# design.net
KiCad netlist of a schematic drawn in Altium Designer
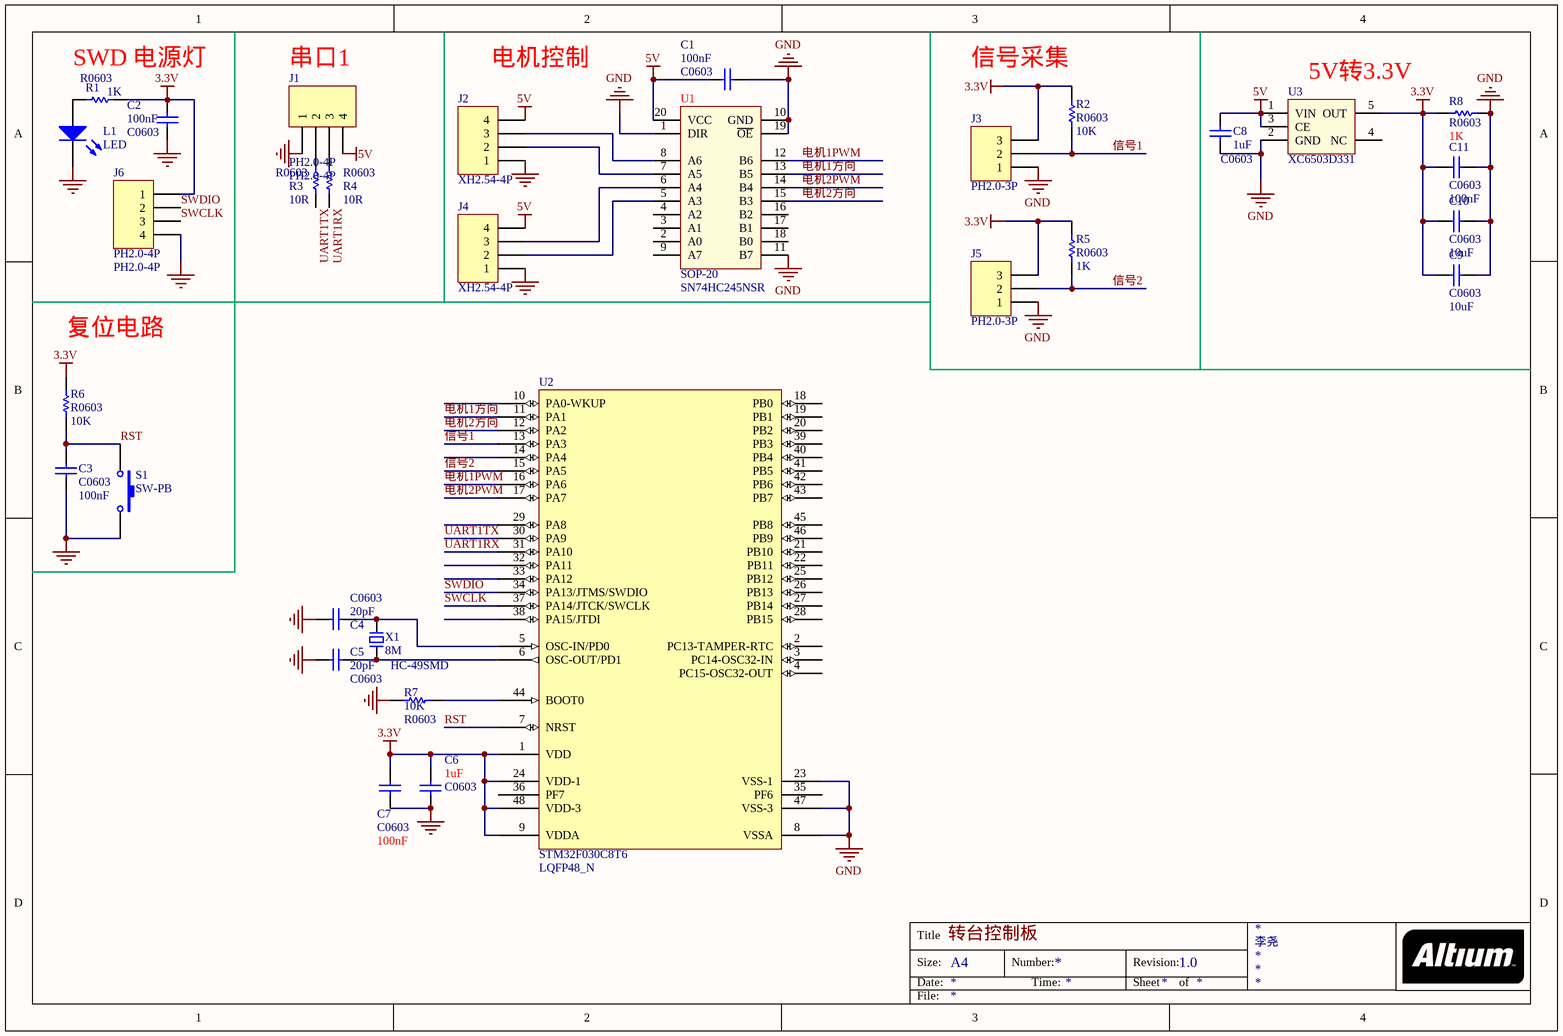
[diagram p0: 转台控制板原理图.SchDoc]

(export (version "E")
  (design (tool "Eeschema 10.0.6"))
  (components
    (comp (ref "C1")
      (value "C0603")
      (footprint "C0603_M1608")
      (description "Capacitor")
      (fields (field (name "ALTIUM_VALUE") "100nF") (field (name "PUBLISHER") "Altium Limited"))
      (libsource (lib "Miscellaneous Devices") (part "Cap"))
    )
    (comp (ref "C2")
      (value "C0603")
      (footprint "C0603_M1608")
      (description "Capacitor")
      (fields (field (name "ALTIUM_VALUE") "100nF") (field (name "PUBLISHER") "Altium Limited"))
      (libsource (lib "Miscellaneous Devices") (part "Cap"))
    )
    (comp (ref "C3")
      (value "C0603")
      (footprint "C0603_M1608")
      (description "Capacitor")
      (fields (field (name "ALTIUM_VALUE") "100nF") (field (name "PUBLISHER") "Altium Limited"))
      (libsource (lib "Miscellaneous Devices") (part "Cap"))
    )
    (comp (ref "C4")
      (value "C0603")
      (footprint "C0603_M1608")
      (description "Capacitor")
      (fields (field (name "ALTIUM_VALUE") "20pF") (field (name "PUBLISHER") "Altium Limited"))
      (libsource (lib "Miscellaneous Devices") (part "Cap"))
    )
    (comp (ref "C5")
      (value "C0603")
      (footprint "C0603_M1608")
      (description "Capacitor")
      (fields (field (name "ALTIUM_VALUE") "20pF") (field (name "PUBLISHER") "Altium Limited"))
      (libsource (lib "Miscellaneous Devices") (part "Cap"))
    )
    (comp (ref "C6")
      (value "C0603")
      (footprint "C0603_M1608")
      (description "Capacitor")
      (fields (field (name "ALTIUM_VALUE") "1uF") (field (name "PUBLISHER") "Altium Limited"))
      (libsource (lib "Miscellaneous Devices") (part "Cap"))
    )
    (comp (ref "C7")
      (value "C0603")
      (footprint "C0603_M1608")
      (description "Capacitor")
      (fields (field (name "ALTIUM_VALUE") "100nF") (field (name "PUBLISHER") "Altium Limited"))
      (libsource (lib "Miscellaneous Devices") (part "Cap"))
    )
    (comp (ref "C8")
      (value "C0603")
      (footprint "C0603_M1608")
      (description "Capacitor")
      (fields (field (name "ALTIUM_VALUE") "1uF") (field (name "PUBLISHER") "Altium Limited"))
      (libsource (lib "Miscellaneous Devices") (part "Cap"))
    )
    (comp (ref "C9")
      (value "C0603")
      (footprint "C0603_M1608")
      (description "Capacitor")
      (fields (field (name "ALTIUM_VALUE") "10uF") (field (name "PUBLISHER") "Altium Limited"))
      (libsource (lib "Miscellaneous Devices") (part "Cap"))
    )
    (comp (ref "C10")
      (value "C0603")
      (footprint "C0603_M1608")
      (description "Capacitor")
      (fields (field (name "ALTIUM_VALUE") "10uF") (field (name "PUBLISHER") "Altium Limited"))
      (libsource (lib "Miscellaneous Devices") (part "Cap"))
    )
    (comp (ref "C11")
      (value "C0603")
      (footprint "C0603_M1608")
      (description "Capacitor")
      (fields (field (name "ALTIUM_VALUE") "100nF") (field (name "PUBLISHER") "Altium Limited"))
      (libsource (lib "Miscellaneous Devices") (part "Cap"))
    )
    (comp (ref "J1")
      (value "PH2.0-4P")
      (footprint "PH2.0-4P")
      (description "Header, 4-Pin")
      (fields (field (name "ALTIUM_VALUE") "PH2.0-4P") (field (name "PUBLISHER") "Altium Limited"))
      (libsource (lib "") (part "Header 4_1"))
    )
    (comp (ref "J2")
      (value "XH2.54-4P")
      (footprint "XH2.54-4")
      (description "Header, 4-Pin")
      (fields (field (name "PUBLISHER") "Altium Limited"))
      (libsource (lib "") (part "Header 4_2"))
    )
    (comp (ref "J3")
      (value "PH2.0-3P")
      (footprint "PH2.0-3P")
      (description "Header, 3-Pin")
      (fields (field (name "PUBLISHER") "Altium Limited"))
      (libsource (lib "Sparks") (part "Header 3"))
    )
    (comp (ref "J4")
      (value "XH2.54-4P")
      (footprint "XH2.54-4")
      (description "Header, 4-Pin")
      (fields (field (name "PUBLISHER") "Altium Limited"))
      (libsource (lib "") (part "Header 4_2"))
    )
    (comp (ref "J5")
      (value "PH2.0-3P")
      (footprint "PH2.0-3P")
      (description "Header, 3-Pin")
      (fields (field (name "PUBLISHER") "Altium Limited"))
      (libsource (lib "Sparks") (part "Header 3"))
    )
    (comp (ref "J6")
      (value "PH2.0-4P")
      (footprint "PH2.0-4P")
      (description "Header, 4-Pin")
      (fields (field (name "ALTIUM_VALUE") "PH2.0-4P") (field (name "PUBLISHER") "Altium Limited"))
      (libsource (lib "Miscellaneous Connectors") (part "Header 4"))
    )
    (comp (ref "L1") (value "LED") (footprint "C2012") (libsource (lib "Sparks") (part "LED")))
    (comp (ref "R1")
      (value "R0603")
      (footprint "0603")
      (description "Resistor")
      (fields (field (name "ALTIUM_VALUE") "1K") (field (name "PUBLISHER") "Altium Limited"))
      (libsource (lib "Miscellaneous Devices") (part "Res1"))
    )
    (comp (ref "R2")
      (value "R0603")
      (footprint "0603")
      (description "Resistor")
      (fields (field (name "ALTIUM_VALUE") "10K") (field (name "PUBLISHER") "Altium Limited"))
      (libsource (lib "Miscellaneous Devices") (part "Res1"))
    )
    (comp (ref "R3")
      (value "R0603")
      (footprint "0603")
      (description "Resistor")
      (fields (field (name "ALTIUM_VALUE") "10R") (field (name "PUBLISHER") "Altium Limited"))
      (libsource (lib "Miscellaneous Devices") (part "Res1"))
    )
    (comp (ref "R4")
      (value "R0603")
      (footprint "0603")
      (description "Resistor")
      (fields (field (name "ALTIUM_VALUE") "10R") (field (name "PUBLISHER") "Altium Limited"))
      (libsource (lib "Miscellaneous Devices") (part "Res1"))
    )
    (comp (ref "R5")
      (value "R0603")
      (footprint "0603")
      (description "Resistor")
      (fields (field (name "ALTIUM_VALUE") "1K") (field (name "PUBLISHER") "Altium Limited"))
      (libsource (lib "Miscellaneous Devices") (part "Res1"))
    )
    (comp (ref "R6")
      (value "R0603")
      (footprint "0603")
      (description "Resistor")
      (fields (field (name "ALTIUM_VALUE") "10K") (field (name "PUBLISHER") "Altium Limited"))
      (libsource (lib "Miscellaneous Devices") (part "Res1"))
    )
    (comp (ref "R7")
      (value "R0603")
      (footprint "0603")
      (description "Resistor")
      (fields (field (name "ALTIUM_VALUE") "10K") (field (name "PUBLISHER") "Altium Limited"))
      (libsource (lib "Miscellaneous Devices") (part "Res1"))
    )
    (comp (ref "R8")
      (value "R0603")
      (footprint "0603")
      (description "Resistor")
      (fields (field (name "ALTIUM_VALUE") "1K") (field (name "PUBLISHER") "Altium Limited"))
      (libsource (lib "Miscellaneous Devices") (part "Res1"))
    )
    (comp (ref "S1")
      (value "SW-PB")
      (footprint "SPST-2")
      (description "Switch")
      (fields (field (name "PUBLISHER") "Altium Limited"))
      (libsource (lib "Miscellaneous Devices") (part "SW-PB"))
    )
    (comp (ref "U1")
      (value "SOP-20")
      (footprint "SOP-20")
      (fields (field (name "ALTIUM_VALUE") "SN74HC245NSR"))
      (libsource (lib "SCH") (part "74HC245"))
    )
    (comp (ref "U2")
      (value "LQFP48_N")
      (footprint "LQFP48_N")
      (description "STM32 ARM-based 32-bit MCU with 64 Kbytes Flash, 48-pin LQFP, Industrial Temperature")
      (fields (field (name "ALTIUM_VALUE") "STM32F030C8T6") (field (name "PUBLISHER") "*"))
      (libsource (lib "ST Microcontroller 32-Bit STM32 SCH") (part "STM32F103C8T6"))
    )
    (comp (ref "U3")
      (value "XC6503D331")
      (footprint "SOT23-5")
      (libsource (lib "CYSchlib") (part "XC6503Dxxx"))
    )
    (comp (ref "X1")
      (value "8M")
      (footprint "HC-49SMD")
      (fields (field (name "ALTIUM_VALUE") "HC-49SMD"))
      (libsource (lib "CYSchlib") (part "XTAL"))
    )
  )
  (nets
    (net (code "1") (name "/RST") (class "Default")
      (node (ref "C3") (pin "1") (pinfunction "1_1") (pintype "passive"))
      (node (ref "R6") (pin "2") (pinfunction "2_2") (pintype "passive"))
      (node (ref "S1") (pin "1") (pinfunction "1_1") (pintype "passive"))
      (node (ref "U2") (pin "7") (pinfunction "NRST_7") (pintype "bidirectional"))
    )
    (net (code "2") (name "/SWCLK") (class "Default")
      (node (ref "J6") (pin "3") (pinfunction "3_3") (pintype "passive"))
      (node (ref "U2") (pin "37") (pinfunction "PA14/JTCK/SWCLK_37") (pintype "bidirectional"))
    )
    (net (code "3") (name "/SWDIO") (class "Default")
      (node (ref "J6") (pin "2") (pinfunction "2_2") (pintype "passive"))
      (node (ref "U2") (pin "34") (pinfunction "PA13/JTMS/SWDIO_34") (pintype "bidirectional"))
    )
    (net (code "4") (name "/UART1RX") (class "Default")
      (node (ref "R4") (pin "2") (pinfunction "2_2") (pintype "passive"))
      (node (ref "U2") (pin "31") (pinfunction "PA10_31") (pintype "bidirectional"))
    )
    (net (code "5") (name "/UART1TX") (class "Default")
      (node (ref "R3") (pin "2") (pinfunction "2_2") (pintype "passive"))
      (node (ref "U2") (pin "30") (pinfunction "PA9_30") (pintype "bidirectional"))
    )
    (net (code "6") (name "/信号1") (class "Default")
      (node (ref "J3") (pin "2") (pinfunction "2_2") (pintype "passive"))
      (node (ref "R2") (pin "2") (pinfunction "2_2") (pintype "passive"))
      (node (ref "U2") (pin "13") (pinfunction "PA3_13") (pintype "bidirectional"))
    )
    (net (code "7") (name "/信号2") (class "Default")
      (node (ref "J5") (pin "2") (pinfunction "2_2") (pintype "passive"))
      (node (ref "R5") (pin "2") (pinfunction "2_2") (pintype "passive"))
      (node (ref "U2") (pin "15") (pinfunction "PA5_15") (pintype "bidirectional"))
    )
    (net (code "8") (name "/电机1PWM") (class "Default")
      (node (ref "U1") (pin "12") (pinfunction "B6_12") (pintype "passive"))
      (node (ref "U2") (pin "16") (pinfunction "PA6_16") (pintype "bidirectional"))
    )
    (net (code "9") (name "/电机1方向") (class "Default")
      (node (ref "U1") (pin "13") (pinfunction "B5_13") (pintype "passive"))
      (node (ref "U2") (pin "11") (pinfunction "PA1_11") (pintype "bidirectional"))
    )
    (net (code "10") (name "/电机2PWM") (class "Default")
      (node (ref "U1") (pin "14") (pinfunction "B4_14") (pintype "passive"))
      (node (ref "U2") (pin "17") (pinfunction "PA7_17") (pintype "bidirectional"))
    )
    (net (code "11") (name "/电机2方向") (class "Default")
      (node (ref "U1") (pin "15") (pinfunction "B3_15") (pintype "passive"))
      (node (ref "U2") (pin "12") (pinfunction "PA2_12") (pintype "bidirectional"))
    )
    (net (code "12") (name "3.3V") (class "Default")
      (node (ref "C10") (pin "2") (pinfunction "2_2") (pintype "passive"))
      (node (ref "C11") (pin "2") (pinfunction "2_2") (pintype "passive"))
      (node (ref "C2") (pin "1") (pinfunction "1_1") (pintype "passive"))
      (node (ref "C6") (pin "1") (pinfunction "1_1") (pintype "passive"))
      (node (ref "C7") (pin "1") (pinfunction "1_1") (pintype "passive"))
      (node (ref "C9") (pin "1") (pinfunction "1_1") (pintype "passive"))
      (node (ref "J3") (pin "3") (pinfunction "3_3") (pintype "passive"))
      (node (ref "J5") (pin "3") (pinfunction "3_3") (pintype "passive"))
      (node (ref "J6") (pin "1") (pinfunction "1_1") (pintype "passive"))
      (node (ref "R1") (pin "2") (pinfunction "2_2") (pintype "passive"))
      (node (ref "R2") (pin "1") (pinfunction "1_1") (pintype "passive"))
      (node (ref "R5") (pin "1") (pinfunction "1_1") (pintype "passive"))
      (node (ref "R6") (pin "1") (pinfunction "1_1") (pintype "passive"))
      (node (ref "R8") (pin "2") (pinfunction "2_2") (pintype "passive"))
      (node (ref "U2") (pin "1") (pinfunction "VDD_1") (pintype "power_in"))
      (node (ref "U2") (pin "24") (pinfunction "VDD-1_24") (pintype "power_in"))
      (node (ref "U2") (pin "48") (pinfunction "VDD-3_48") (pintype "power_in"))
      (node (ref "U2") (pin "9") (pinfunction "VDDA_9") (pintype "power_in"))
      (node (ref "U3") (pin "5") (pinfunction "OUT_5") (pintype "passive"))
    )
    (net (code "13") (name "5V") (class "Default")
      (node (ref "C1") (pin "1") (pinfunction "1_1") (pintype "passive"))
      (node (ref "C8") (pin "2") (pinfunction "2_2") (pintype "passive"))
      (node (ref "J1") (pin "4") (pinfunction "4_4") (pintype "passive"))
      (node (ref "J2") (pin "4") (pinfunction "4_4") (pintype "passive"))
      (node (ref "J4") (pin "4") (pinfunction "4_4") (pintype "passive"))
      (node (ref "U1") (pin "20") (pinfunction "VCC_20") (pintype "passive"))
      (node (ref "U3") (pin "1") (pinfunction "VIN_1") (pintype "passive"))
      (node (ref "U3") (pin "3") (pinfunction "CE_3") (pintype "passive"))
    )
    (net (code "14") (name "GND") (class "Default")
      (node (ref "C1") (pin "2") (pinfunction "2_2") (pintype "passive"))
      (node (ref "C10") (pin "1") (pinfunction "1_1") (pintype "passive"))
      (node (ref "C11") (pin "1") (pinfunction "1_1") (pintype "passive"))
      (node (ref "C2") (pin "2") (pinfunction "2_2") (pintype "passive"))
      (node (ref "C3") (pin "2") (pinfunction "2_2") (pintype "passive"))
      (node (ref "C4") (pin "1") (pinfunction "1_1") (pintype "passive"))
      (node (ref "C5") (pin "1") (pinfunction "1_1") (pintype "passive"))
      (node (ref "C6") (pin "2") (pinfunction "2_2") (pintype "passive"))
      (node (ref "C7") (pin "2") (pinfunction "2_2") (pintype "passive"))
      (node (ref "C8") (pin "1") (pinfunction "1_1") (pintype "passive"))
      (node (ref "C9") (pin "2") (pinfunction "2_2") (pintype "passive"))
      (node (ref "J1") (pin "1") (pinfunction "1_1") (pintype "passive"))
      (node (ref "J2") (pin "1") (pinfunction "1_1") (pintype "passive"))
      (node (ref "J3") (pin "1") (pinfunction "1_1") (pintype "passive"))
      (node (ref "J4") (pin "1") (pinfunction "1_1") (pintype "passive"))
      (node (ref "J5") (pin "1") (pinfunction "1_1") (pintype "passive"))
      (node (ref "J6") (pin "4") (pinfunction "4_4") (pintype "passive"))
      (node (ref "L1") (pin "2") (pinfunction "K_2") (pintype "passive"))
      (node (ref "R7") (pin "1") (pinfunction "1_1") (pintype "passive"))
      (node (ref "R8") (pin "1") (pinfunction "1_1") (pintype "passive"))
      (node (ref "S1") (pin "2") (pinfunction "2_2") (pintype "passive"))
      (node (ref "U1") (pin "1") (pinfunction "DIR_1") (pintype "passive"))
      (node (ref "U1") (pin "10") (pinfunction "GND_10") (pintype "passive"))
      (node (ref "U1") (pin "11") (pinfunction "B7_11") (pintype "passive"))
      (node (ref "U1") (pin "19") (pinfunction "~{OE}_19") (pintype "passive"))
      (node (ref "U2") (pin "23") (pinfunction "VSS-1_23") (pintype "power_in"))
      (node (ref "U2") (pin "47") (pinfunction "VSS-3_47") (pintype "power_in"))
      (node (ref "U2") (pin "8") (pinfunction "VSSA_8") (pintype "power_in"))
      (node (ref "U3") (pin "2") (pinfunction "GND_2") (pintype "passive"))
    )
    (net (code "15") (name "Net-(J1-Pad2)") (class "Default")
      (node (ref "J1") (pin "2") (pinfunction "2_2") (pintype "passive"))
      (node (ref "R3") (pin "1") (pinfunction "1_1") (pintype "passive"))
    )
    (net (code "16") (name "Net-(J1-Pad3)") (class "Default")
      (node (ref "J1") (pin "3") (pinfunction "3_3") (pintype "passive"))
      (node (ref "R4") (pin "1") (pinfunction "1_1") (pintype "passive"))
    )
    (net (code "17") (name "Net-(L1-A)") (class "Default")
      (node (ref "L1") (pin "1") (pinfunction "A_1") (pintype "passive"))
      (node (ref "R1") (pin "1") (pinfunction "1_1") (pintype "passive"))
    )
    (net (code "18") (name "Net-(U1-A3)") (class "Default")
      (node (ref "J4") (pin "2") (pinfunction "2_2") (pintype "passive"))
      (node (ref "U1") (pin "5") (pinfunction "A3_5") (pintype "passive"))
    )
    (net (code "19") (name "Net-(U1-A4)") (class "Default")
      (node (ref "J4") (pin "3") (pinfunction "3_3") (pintype "passive"))
      (node (ref "U1") (pin "6") (pinfunction "A4_6") (pintype "passive"))
    )
    (net (code "20") (name "Net-(U1-A5)") (class "Default")
      (node (ref "J2") (pin "2") (pinfunction "2_2") (pintype "passive"))
      (node (ref "U1") (pin "7") (pinfunction "A5_7") (pintype "passive"))
    )
    (net (code "21") (name "Net-(U1-A6)") (class "Default")
      (node (ref "J2") (pin "3") (pinfunction "3_3") (pintype "passive"))
      (node (ref "U1") (pin "8") (pinfunction "A6_8") (pintype "passive"))
    )
    (net (code "22") (name "Net-(U2-BOOT0)") (class "Default")
      (node (ref "R7") (pin "2") (pinfunction "2_2") (pintype "passive"))
      (node (ref "U2") (pin "44") (pinfunction "BOOT0_44") (pintype "input"))
    )
    (net (code "23") (name "Net-(U2-OSC-IN{slash}PD0)") (class "Default")
      (node (ref "C4") (pin "2") (pinfunction "2_2") (pintype "passive"))
      (node (ref "U2") (pin "5") (pinfunction "OSC-IN/PD0_5") (pintype "input"))
      (node (ref "X1") (pin "2") (pinfunction "2_2") (pintype "passive"))
    )
    (net (code "24") (name "Net-(U2-OSC-OUT{slash}PD1)") (class "Default")
      (node (ref "C5") (pin "2") (pinfunction "2_2") (pintype "passive"))
      (node (ref "U2") (pin "6") (pinfunction "OSC-OUT/PD1_6") (pintype "output"))
      (node (ref "X1") (pin "1") (pinfunction "1_1") (pintype "passive"))
    )
    (net (code "25") (name "unconnected-(U1-A0-Pad2)") (class "Default")
      (node (ref "U1") (pin "2") (pinfunction "A0_2") (pintype "passive"))
    )
    (net (code "26") (name "unconnected-(U1-A1-Pad3)") (class "Default")
      (node (ref "U1") (pin "3") (pinfunction "A1_3") (pintype "passive"))
    )
    (net (code "27") (name "unconnected-(U1-A2-Pad4)") (class "Default")
      (node (ref "U1") (pin "4") (pinfunction "A2_4") (pintype "passive"))
    )
    (net (code "28") (name "unconnected-(U1-A7-Pad9)") (class "Default")
      (node (ref "U1") (pin "9") (pinfunction "A7_9") (pintype "passive"))
    )
    (net (code "29") (name "unconnected-(U1-B0-Pad18)") (class "Default")
      (node (ref "U1") (pin "18") (pinfunction "B0_18") (pintype "passive"))
    )
    (net (code "30") (name "unconnected-(U1-B1-Pad17)") (class "Default")
      (node (ref "U1") (pin "17") (pinfunction "B1_17") (pintype "passive"))
    )
    (net (code "31") (name "unconnected-(U1-B2-Pad16)") (class "Default")
      (node (ref "U1") (pin "16") (pinfunction "B2_16") (pintype "passive"))
    )
    (net (code "32") (name "unconnected-(U2-PA0-WKUP-Pad10)") (class "Default")
      (node (ref "U2") (pin "10") (pinfunction "PA0-WKUP_10") (pintype "bidirectional"))
    )
    (net (code "33") (name "unconnected-(U2-PA4-Pad14)") (class "Default")
      (node (ref "U2") (pin "14") (pinfunction "PA4_14") (pintype "bidirectional"))
    )
    (net (code "34") (name "unconnected-(U2-PA8-Pad29)") (class "Default")
      (node (ref "U2") (pin "29") (pinfunction "PA8_29") (pintype "bidirectional"))
    )
    (net (code "35") (name "unconnected-(U2-PA11-Pad32)") (class "Default")
      (node (ref "U2") (pin "32") (pinfunction "PA11_32") (pintype "bidirectional"))
    )
    (net (code "36") (name "unconnected-(U2-PA12-Pad33)") (class "Default")
      (node (ref "U2") (pin "33") (pinfunction "PA12_33") (pintype "bidirectional"))
    )
    (net (code "37") (name "unconnected-(U2-PA15{slash}JTDI-Pad38)") (class "Default")
      (node (ref "U2") (pin "38") (pinfunction "PA15/JTDI_38") (pintype "bidirectional"))
    )
    (net (code "38") (name "unconnected-(U2-PB0-Pad18)") (class "Default")
      (node (ref "U2") (pin "18") (pinfunction "PB0_18") (pintype "bidirectional"))
    )
    (net (code "39") (name "unconnected-(U2-PB1-Pad19)") (class "Default")
      (node (ref "U2") (pin "19") (pinfunction "PB1_19") (pintype "bidirectional"))
    )
    (net (code "40") (name "unconnected-(U2-PB2-Pad20)") (class "Default")
      (node (ref "U2") (pin "20") (pinfunction "PB2_20") (pintype "bidirectional"))
    )
    (net (code "41") (name "unconnected-(U2-PB3-Pad39)") (class "Default")
      (node (ref "U2") (pin "39") (pinfunction "PB3_39") (pintype "bidirectional"))
    )
    (net (code "42") (name "unconnected-(U2-PB4-Pad40)") (class "Default")
      (node (ref "U2") (pin "40") (pinfunction "PB4_40") (pintype "bidirectional"))
    )
    (net (code "43") (name "unconnected-(U2-PB5-Pad41)") (class "Default")
      (node (ref "U2") (pin "41") (pinfunction "PB5_41") (pintype "bidirectional"))
    )
    (net (code "44") (name "unconnected-(U2-PB6-Pad42)") (class "Default")
      (node (ref "U2") (pin "42") (pinfunction "PB6_42") (pintype "bidirectional"))
    )
    (net (code "45") (name "unconnected-(U2-PB7-Pad43)") (class "Default")
      (node (ref "U2") (pin "43") (pinfunction "PB7_43") (pintype "bidirectional"))
    )
    (net (code "46") (name "unconnected-(U2-PB8-Pad45)") (class "Default")
      (node (ref "U2") (pin "45") (pinfunction "PB8_45") (pintype "bidirectional"))
    )
    (net (code "47") (name "unconnected-(U2-PB9-Pad46)") (class "Default")
      (node (ref "U2") (pin "46") (pinfunction "PB9_46") (pintype "bidirectional"))
    )
    (net (code "48") (name "unconnected-(U2-PB10-Pad21)") (class "Default")
      (node (ref "U2") (pin "21") (pinfunction "PB10_21") (pintype "bidirectional"))
    )
    (net (code "49") (name "unconnected-(U2-PB11-Pad22)") (class "Default")
      (node (ref "U2") (pin "22") (pinfunction "PB11_22") (pintype "bidirectional"))
    )
    (net (code "50") (name "unconnected-(U2-PB12-Pad25)") (class "Default")
      (node (ref "U2") (pin "25") (pinfunction "PB12_25") (pintype "bidirectional"))
    )
    (net (code "51") (name "unconnected-(U2-PB13-Pad26)") (class "Default")
      (node (ref "U2") (pin "26") (pinfunction "PB13_26") (pintype "bidirectional"))
    )
    (net (code "52") (name "unconnected-(U2-PB14-Pad27)") (class "Default")
      (node (ref "U2") (pin "27") (pinfunction "PB14_27") (pintype "bidirectional"))
    )
    (net (code "53") (name "unconnected-(U2-PB15-Pad28)") (class "Default")
      (node (ref "U2") (pin "28") (pinfunction "PB15_28") (pintype "bidirectional"))
    )
    (net (code "54") (name "unconnected-(U2-PC13-TAMPER-RTC-Pad2)") (class "Default")
      (node (ref "U2") (pin "2") (pinfunction "PC13-TAMPER-RTC_2") (pintype "bidirectional"))
    )
    (net (code "55") (name "unconnected-(U2-PC14-OSC32-IN-Pad3)") (class "Default")
      (node (ref "U2") (pin "3") (pinfunction "PC14-OSC32-IN_3") (pintype "bidirectional"))
    )
    (net (code "56") (name "unconnected-(U2-PC15-OSC32-OUT-Pad4)") (class "Default")
      (node (ref "U2") (pin "4") (pinfunction "PC15-OSC32-OUT_4") (pintype "bidirectional"))
    )
    (net (code "57") (name "unconnected-(U2-PF6-Pad35)") (class "Default")
      (node (ref "U2") (pin "35") (pinfunction "PF6_35") (pintype "power_in"))
    )
    (net (code "58") (name "unconnected-(U2-PF7-Pad36)") (class "Default")
      (node (ref "U2") (pin "36") (pinfunction "PF7_36") (pintype "power_in"))
    )
    (net (code "59") (name "unconnected-(U3-NC-Pad4)") (class "Default")
      (node (ref "U3") (pin "4") (pinfunction "NC_4") (pintype "passive"))
    )
  )
)
